# RF.net
KiCad netlist of a schematic drawn in Altium Designer
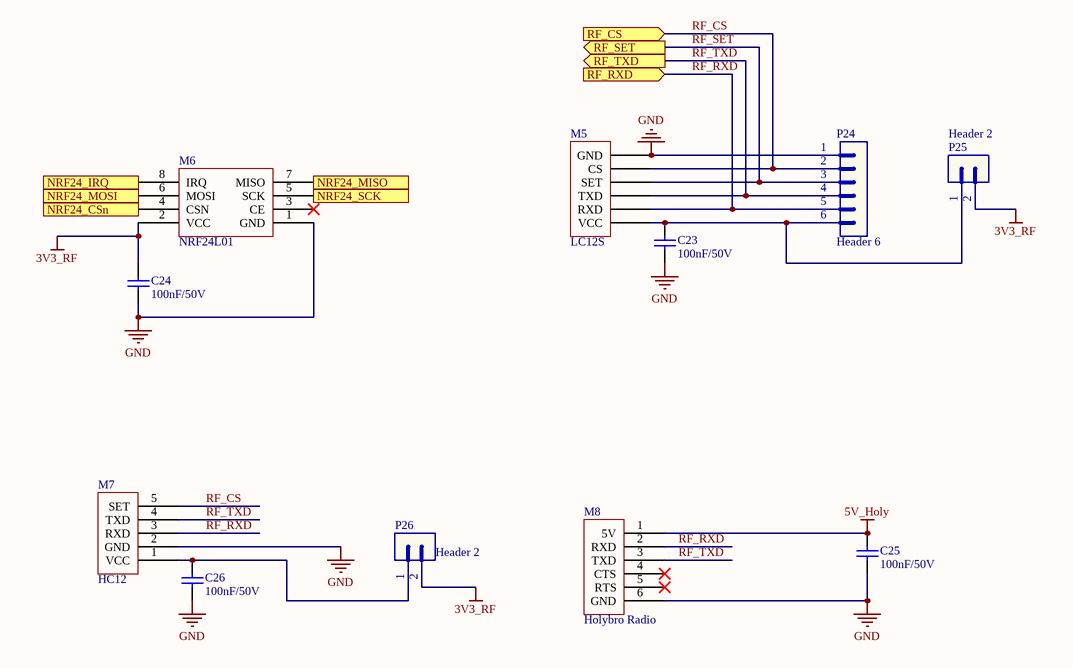
[diagram p0: RF.SchDoc]

(export (version "E")
  (design (tool "Eeschema 10.0.6"))
  (components
    (comp (ref "C23")
      (value "100nF/50V")
      (footprint "CAP-SM-0805")
      (description "CAP CER 0.1UF 50V Y5V 0805")
      (fields
        (field (name "MANUFACTURER") "Samsung Electro-Mechanics")
        (field (name "MANUFACTURER PART NUMBER") "CL21F104ZBCNNNC")
      )
      (libsource (lib "Capacitor") (part "Cap-100nF-50V-0805"))
    )
    (comp (ref "C24")
      (value "100nF/50V")
      (footprint "CAP-SM-0805")
      (description "CAP CER 0.1UF 50V Y5V 0805")
      (fields
        (field (name "MANUFACTURER") "Samsung Electro-Mechanics")
        (field (name "MANUFACTURER PART NUMBER") "CL21F104ZBCNNNC")
      )
      (libsource (lib "Capacitor") (part "Cap-100nF-50V-0805"))
    )
    (comp (ref "C25")
      (value "100nF/50V")
      (footprint "CAP-SM-0805")
      (description "CAP CER 0.1UF 50V Y5V 0805")
      (fields
        (field (name "MANUFACTURER") "Samsung Electro-Mechanics")
        (field (name "MANUFACTURER PART NUMBER") "CL21F104ZBCNNNC")
      )
      (libsource (lib "Capacitor") (part "Cap-100nF-50V-0805"))
    )
    (comp (ref "C26")
      (value "100nF/50V")
      (footprint "CAP-SM-0805")
      (description "CAP CER 0.1UF 50V Y5V 0805")
      (fields
        (field (name "MANUFACTURER") "Samsung Electro-Mechanics")
        (field (name "MANUFACTURER PART NUMBER") "CL21F104ZBCNNNC")
      )
      (libsource (lib "Capacitor") (part "Cap-100nF-50V-0805"))
    )
    (comp (ref "M5")
      (value "LC12S")
      (footprint "LC12S")
      (fields (field (name "LOCAL SUPPLIER PART NUMBER") "HS000895"))
      (libsource (lib "xecanbang") (part "LC12S"))
    )
    (comp (ref "M6")
      (value "NRF24L01")
      (footprint "NRF24L01")
      (fields (field (name "LOCAL SUPPLIER PART NUMBER") "HS000888"))
      (libsource (lib "xecanbang") (part "NRF24L01"))
    )
    (comp (ref "M7")
      (value "HC12")
      (footprint "HC12")
      (fields (field (name "LOCAL SUPPLIER PART NUMBER") "HS000897"))
      (libsource (lib "xecanbang") (part "HC12"))
    )
    (comp (ref "M8")
      (value "Holybro Radio")
      (footprint "Holybro-RADIO")
      (libsource (lib "xecanbang") (part "Holybro Radio"))
    )
    (comp (ref "P24")
      (value "Header 6")
      (footprint "JP6")
      (description "Header, 6-Pin")
      (fields (field (name "PUBLISHER") "Altium Limited"))
      (libsource (lib "Header-connector") (part "Header 6"))
    )
    (comp (ref "P25")
      (value "Header 2")
      (footprint "JP2")
      (description "Header, 2-Pin")
      (fields (field (name "PUBLISHER") "Altium Limited"))
      (libsource (lib "Header-connector") (part "Header 2"))
    )
    (comp (ref "P26")
      (value "Header 2")
      (footprint "JP2")
      (description "Header, 2-Pin")
      (fields (field (name "PUBLISHER") "Altium Limited"))
      (libsource (lib "Header-connector") (part "Header 2"))
    )
  )
  (nets
    (net (code "1") (name "/NRF24_CSn") (class "Default")
      (node (ref "M6") (pin "4") (pinfunction "CSN_4") (pintype "passive"))
    )
    (net (code "2") (name "/NRF24_IRQ") (class "Default")
      (node (ref "M6") (pin "8") (pinfunction "IRQ_8") (pintype "passive"))
    )
    (net (code "3") (name "/NRF24_MISO") (class "Default")
      (node (ref "M6") (pin "7") (pinfunction "MISO_7") (pintype "passive"))
    )
    (net (code "4") (name "/NRF24_MOSI") (class "Default")
      (node (ref "M6") (pin "6") (pinfunction "MOSI_6") (pintype "passive"))
    )
    (net (code "5") (name "/NRF24_SCK") (class "Default")
      (node (ref "M6") (pin "5") (pinfunction "SCK_5") (pintype "passive"))
    )
    (net (code "6") (name "/RF_CS") (class "Default")
      (node (ref "M5") (pin "5") (pinfunction "CS_5") (pintype "passive"))
      (node (ref "M7") (pin "5") (pinfunction "SET_5") (pintype "passive"))
      (node (ref "P24") (pin "2") (pinfunction "2_2") (pintype "passive"))
    )
    (net (code "7") (name "/RF_RXD") (class "Default")
      (node (ref "M5") (pin "2") (pinfunction "RXD_2") (pintype "passive"))
      (node (ref "M7") (pin "3") (pinfunction "RXD_3") (pintype "passive"))
      (node (ref "M8") (pin "2") (pinfunction "RXD_2") (pintype "passive"))
      (node (ref "P24") (pin "5") (pinfunction "5_5") (pintype "passive"))
    )
    (net (code "8") (name "/RF_SET") (class "Default")
      (node (ref "M5") (pin "4") (pinfunction "SET_4") (pintype "passive"))
      (node (ref "P24") (pin "3") (pinfunction "3_3") (pintype "passive"))
    )
    (net (code "9") (name "/RF_TXD") (class "Default")
      (node (ref "M5") (pin "3") (pinfunction "TXD_3") (pintype "passive"))
      (node (ref "M7") (pin "4") (pinfunction "TXD_4") (pintype "passive"))
      (node (ref "M8") (pin "3") (pinfunction "TXD_3") (pintype "passive"))
      (node (ref "P24") (pin "4") (pinfunction "4_4") (pintype "passive"))
    )
    (net (code "10") (name "3V3_RF") (class "Default")
      (node (ref "C24") (pin "2") (pinfunction "2_2") (pintype "passive"))
      (node (ref "M6") (pin "2") (pinfunction "VCC_2") (pintype "passive"))
      (node (ref "P25") (pin "2") (pinfunction "2_2") (pintype "passive"))
      (node (ref "P26") (pin "2") (pinfunction "2_2") (pintype "passive"))
    )
    (net (code "11") (name "5V_Holy") (class "Default")
      (node (ref "C25") (pin "2") (pinfunction "2_2") (pintype "passive"))
      (node (ref "M8") (pin "1") (pinfunction "5V_1") (pintype "passive"))
    )
    (net (code "12") (name "GND") (class "Default")
      (node (ref "C23") (pin "1") (pinfunction "1_1") (pintype "passive"))
      (node (ref "C24") (pin "1") (pinfunction "1_1") (pintype "passive"))
      (node (ref "C25") (pin "1") (pinfunction "1_1") (pintype "passive"))
      (node (ref "C26") (pin "1") (pinfunction "1_1") (pintype "passive"))
      (node (ref "M5") (pin "6") (pinfunction "GND_6") (pintype "passive"))
      (node (ref "M6") (pin "1") (pinfunction "GND_1") (pintype "passive"))
      (node (ref "M7") (pin "2") (pinfunction "GND_2") (pintype "passive"))
      (node (ref "M8") (pin "6") (pinfunction "GND_6") (pintype "passive"))
      (node (ref "P24") (pin "1") (pinfunction "1_1") (pintype "passive"))
    )
    (net (code "13") (name "Net-(M5-VCC)") (class "Default")
      (node (ref "C23") (pin "2") (pinfunction "2_2") (pintype "passive"))
      (node (ref "M5") (pin "1") (pinfunction "VCC_1") (pintype "passive"))
      (node (ref "P24") (pin "6") (pinfunction "6_6") (pintype "passive"))
      (node (ref "P25") (pin "1") (pinfunction "1_1") (pintype "passive"))
    )
    (net (code "14") (name "Net-(M7-VCC)") (class "Default")
      (node (ref "C26") (pin "2") (pinfunction "2_2") (pintype "passive"))
      (node (ref "M7") (pin "1") (pinfunction "VCC_1") (pintype "passive"))
      (node (ref "P26") (pin "1") (pinfunction "1_1") (pintype "passive"))
    )
    (net (code "15") (name "unconnected-(M6-CE-Pad3)") (class "Default")
      (node (ref "M6") (pin "3") (pinfunction "CE_3") (pintype "passive+no_connect"))
    )
    (net (code "16") (name "unconnected-(M8-CTS-Pad4)") (class "Default")
      (node (ref "M8") (pin "4") (pinfunction "CTS_4") (pintype "passive+no_connect"))
    )
    (net (code "17") (name "unconnected-(M8-RTS-Pad5)") (class "Default")
      (node (ref "M8") (pin "5") (pinfunction "RTS_5") (pintype "passive+no_connect"))
    )
  )
)
